# Schematic_2.net
KiCad netlist of a schematic drawn in Altium Designer
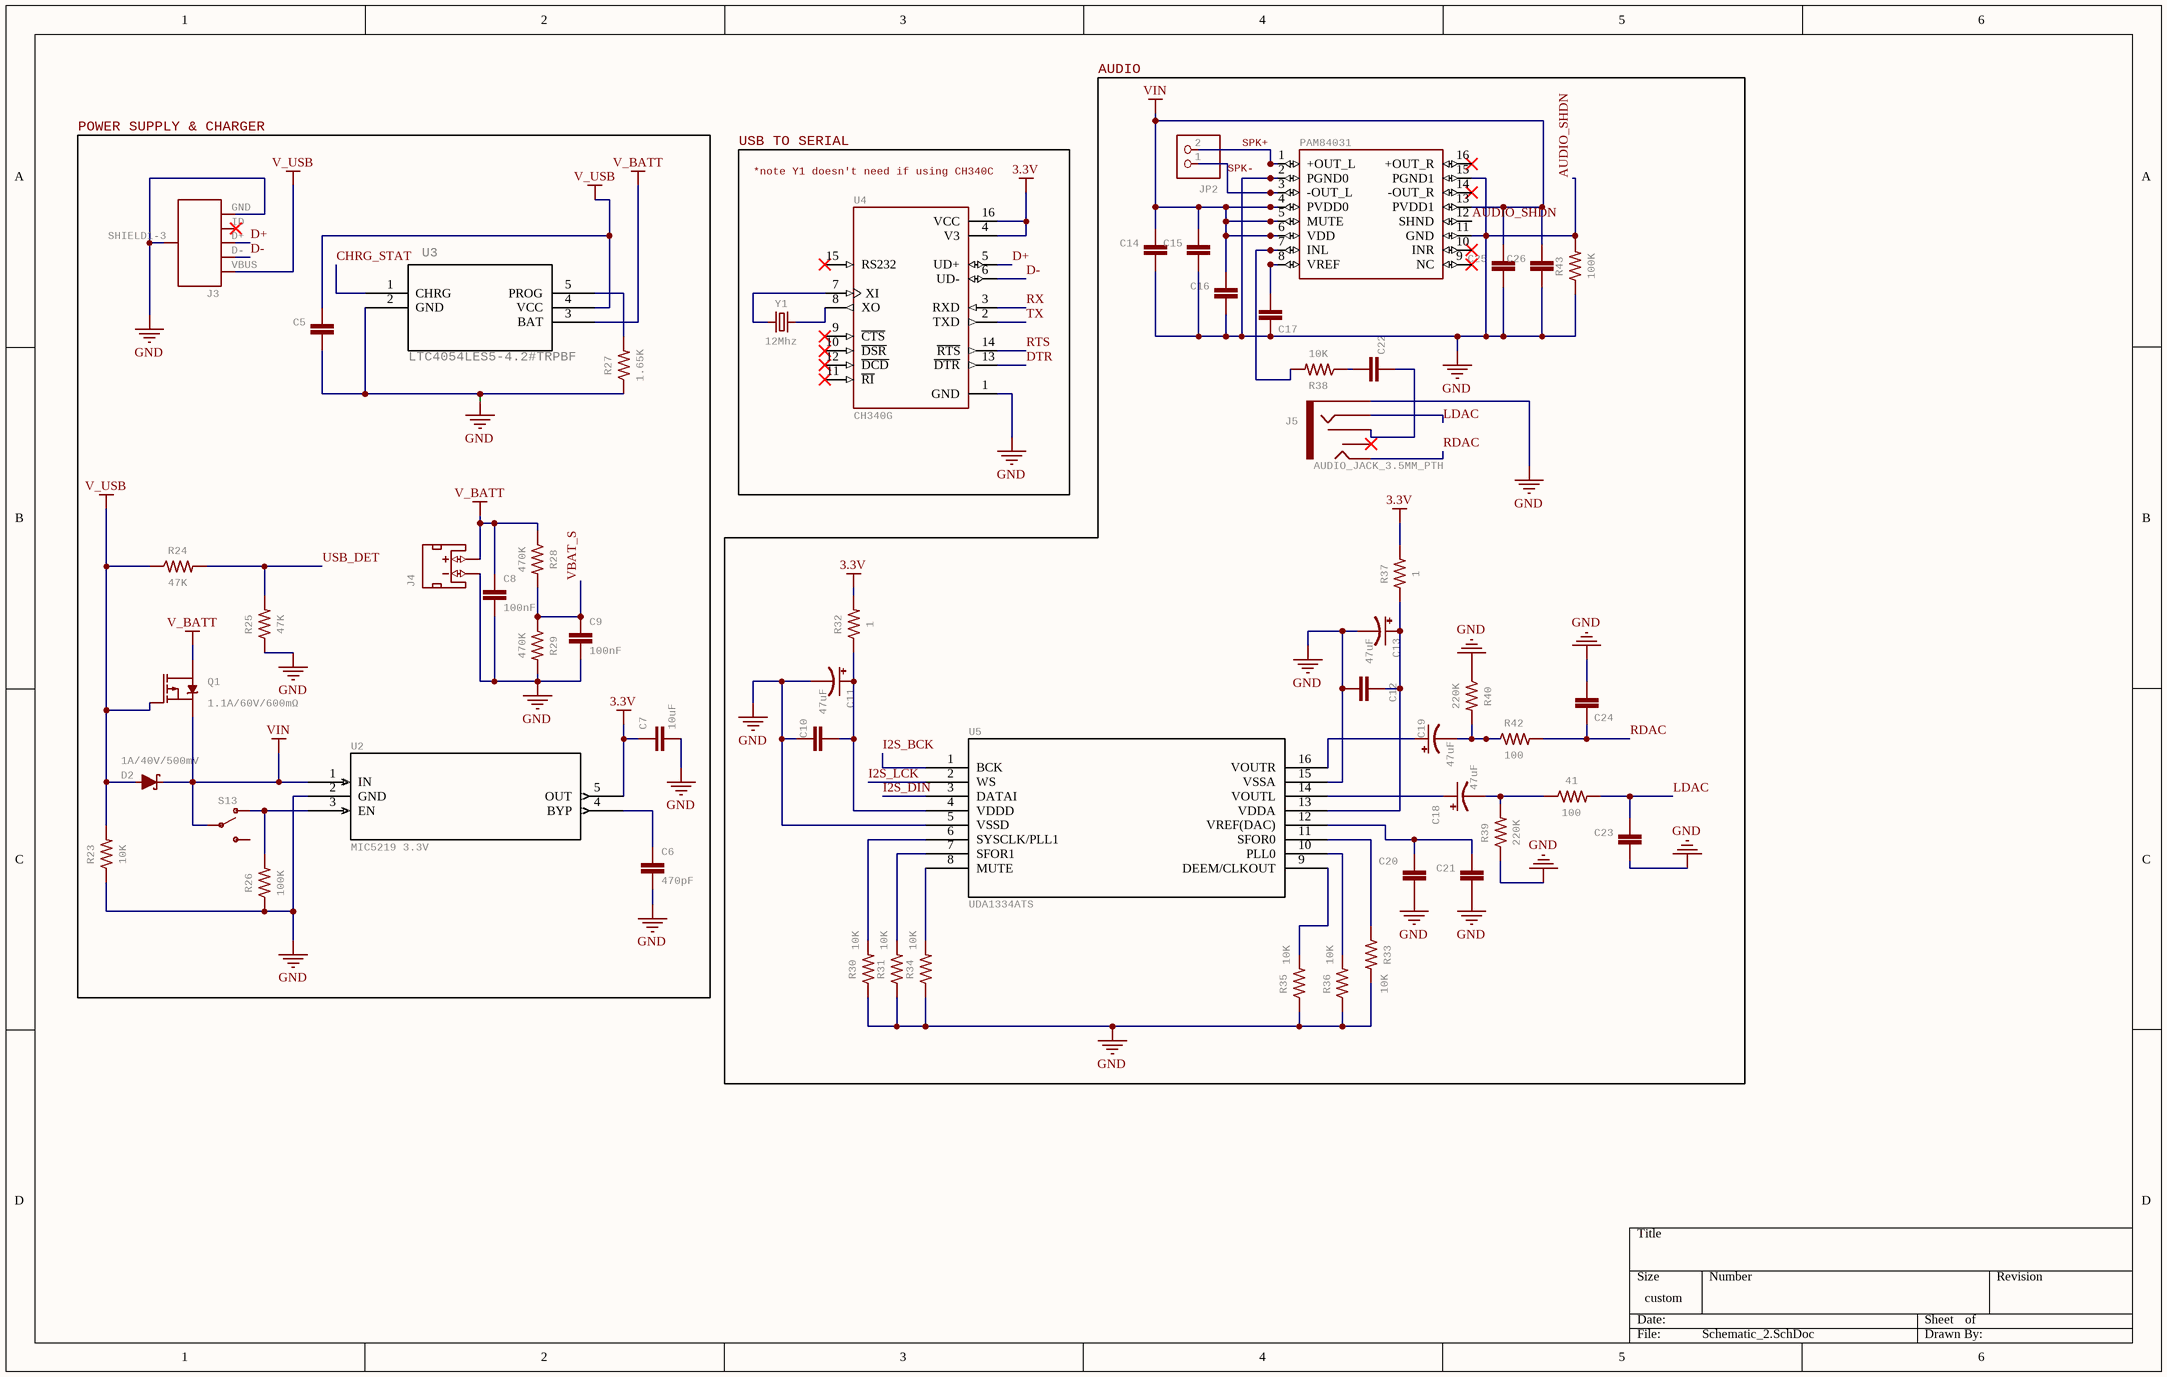
[diagram p0: Schematic_2.SchDoc]

(export (version "E")
  (design (tool "Eeschema 10.0.6"))
  (components
    (comp (ref "41")
      (value "100")
      (footprint "0805 RESISTOR")
      (libsource (lib "2D Components_v1") (part "0.3OHM-0805-1/8W-1%"))
    )
    (comp (ref "C5") (value "~") (footprint "0805") (libsource (lib "") (part "2.2UF-0805-25V-(+80/-20%)_3")))
    (comp (ref "C6")
      (value "470pF")
      (footprint "0805")
      (libsource (lib "2D Components_v1") (part "2.2UF-0805-25V-(+80/-20%)"))
    )
    (comp (ref "C7")
      (value "10uF")
      (footprint "0805")
      (libsource (lib "") (part "2.2UF-0805-25V-(+80/-20%)_1"))
    )
    (comp (ref "C8")
      (value "100nF")
      (footprint "0805")
      (libsource (lib "2D Components_v1") (part "2.2UF-0805-25V-(+80/-20%)"))
    )
    (comp (ref "C9")
      (value "100nF")
      (footprint "0805")
      (libsource (lib "2D Components_v1") (part "2.2UF-0805-25V-(+80/-20%)"))
    )
    (comp (ref "C10")
      (value "~")
      (footprint "0805")
      (libsource (lib "") (part "2.2UF-0805-25V-(+80/-20%)_1"))
    )
    (comp (ref "C11")
      (value "47uF")
      (footprint "EIA3528")
      (libsource (lib "") (part "47UF-POLAR-EIA3528-10V-10%_1"))
    )
    (comp (ref "C12")
      (value "~")
      (footprint "0805")
      (libsource (lib "") (part "2.2UF-0805-25V-(+80/-20%)_1"))
    )
    (comp (ref "C13")
      (value "47uF")
      (footprint "EIA3528")
      (libsource (lib "") (part "47UF-POLAR-EIA3528-10V-10%_1"))
    )
    (comp (ref "C14")
      (value "~")
      (footprint "0805")
      (libsource (lib "") (part "2.2UF-0805-25V-(+80/-20%)_3"))
    )
    (comp (ref "C15")
      (value "~")
      (footprint "0805")
      (libsource (lib "") (part "2.2UF-0805-25V-(+80/-20%)_3"))
    )
    (comp (ref "C16")
      (value "~")
      (footprint "0805")
      (libsource (lib "") (part "2.2UF-0805-25V-(+80/-20%)_3"))
    )
    (comp (ref "C17")
      (value "~")
      (footprint "0805")
      (libsource (lib "") (part "2.2UF-0805-25V-(+80/-20%)_2"))
    )
    (comp (ref "C18")
      (value "47uF")
      (footprint "EIA3528")
      (libsource (lib "2D Components_v1") (part "47UF-POLAR-EIA3528-10V-10%"))
    )
    (comp (ref "C19")
      (value "47uF")
      (footprint "EIA3528")
      (libsource (lib "2D Components_v1") (part "47UF-POLAR-EIA3528-10V-10%"))
    )
    (comp (ref "C20")
      (value "~")
      (footprint "0805")
      (libsource (lib "") (part "2.2UF-0805-25V-(+80/-20%)_3"))
    )
    (comp (ref "C21")
      (value "~")
      (footprint "0805")
      (libsource (lib "") (part "2.2UF-0805-25V-(+80/-20%)_3"))
    )
    (comp (ref "C22")
      (value "~")
      (footprint "0805")
      (libsource (lib "") (part "2.2UF-0805-25V-(+80/-20%)_1"))
    )
    (comp (ref "C23")
      (value "~")
      (footprint "0805")
      (libsource (lib "") (part "2.2UF-0805-25V-(+80/-20%)_3"))
    )
    (comp (ref "C24")
      (value "~")
      (footprint "0805")
      (libsource (lib "2D Components_v1") (part "2.2UF-0805-25V-(+80/-20%)"))
    )
    (comp (ref "C25")
      (value "~")
      (footprint "0805")
      (libsource (lib "") (part "2.2UF-0805-25V-(+80/-20%)_3"))
    )
    (comp (ref "C26")
      (value "~")
      (footprint "0805")
      (libsource (lib "") (part "2.2UF-0805-25V-(+80/-20%)_3"))
    )
    (comp (ref "D2")
      (value "1A/40V/500mV")
      (footprint "SMA-DIODE")
      (libsource (lib "2D Components_v1") (part "DIODE-SCHOTTKY-SS14"))
    )
    (comp (ref "J3")
      (value "~")
      (footprint "USB-B-MICRO-SMD")
      (description "USB_MICRO-B_FEMALE-SMT_J3")
      (libsource (lib "2D Components_v1") (part "USB_MICRO-B_FEMALE-SMT_J3"))
    )
    (comp (ref "J4")
      (value "~")
      (footprint "JST-2-SMD")
      (description "JST_2MM_MALE")
      (libsource (lib "2D Components_v1") (part "JST_2MM_MALE_J4"))
    )
    (comp (ref "J5")
      (value "AUDIO_JACK_3.5MM_PTH")
      (footprint "AUDIO-JACK")
      (libsource (lib "2D Components_v1") (part "AUDIO_JACK_3.5MM_PTH_J5"))
    )
    (comp (ref "JP2")
      (value "~")
      (footprint "1X02M")
      (description "PINHD-1X2_2.00")
      (fields (field (name "LIBRARYNAME") "pinhead-1"))
      (libsource (lib "2D Components_v1") (part "PINHD-1X2_2.00_JP2"))
    )
    (comp (ref "PAM84031")
      (value "PAM8403")
      (footprint "SOP-16")
      (description "Dual channel audio amplifier IC - PAM8403")
      (libsource (lib "2D Components_v1") (part "PAM8403_YES"))
    )
    (comp (ref "Q1")
      (value "1.1A/60V/600mΩ")
      (footprint "SOT23-3")
      (libsource (lib "2D Components_v1") (part "MOSFET_PCH-SI2309DS"))
    )
    (comp (ref "R23")
      (value "10K")
      (footprint "0805")
      (libsource (lib "2D Components_v1") (part "0.22OHM-0805-1/4W-1%"))
    )
    (comp (ref "R24")
      (value "47K")
      (footprint "0805")
      (libsource (lib "2D Components_v1") (part "0.22OHM-0805-1/4W-1%"))
    )
    (comp (ref "R25")
      (value "47K")
      (footprint "0805")
      (libsource (lib "2D Components_v1") (part "0.22OHM-0805-1/4W-1%"))
    )
    (comp (ref "R26")
      (value "100K")
      (footprint "0805")
      (libsource (lib "2D Components_v1") (part "0.22OHM-0805-1/4W-1%"))
    )
    (comp (ref "R27")
      (value "1.65K")
      (footprint "0805")
      (libsource (lib "2D Components_v1") (part "0.3OHM-0805-1/8W-1%"))
    )
    (comp (ref "R28")
      (value "470K")
      (footprint "0805")
      (libsource (lib "2D Components_v1") (part "0.22OHM-0805-1/4W-1%"))
    )
    (comp (ref "R29")
      (value "470K")
      (footprint "0805")
      (libsource (lib "2D Components_v1") (part "0.22OHM-0805-1/4W-1%"))
    )
    (comp (ref "R30")
      (value "10K")
      (footprint "0805")
      (libsource (lib "2D Components_v1") (part "0.3OHM-0805-1/8W-1%"))
    )
    (comp (ref "R31")
      (value "10K")
      (footprint "0805")
      (libsource (lib "2D Components_v1") (part "0.3OHM-0805-1/8W-1%"))
    )
    (comp (ref "R32")
      (value "1")
      (footprint "0805")
      (libsource (lib "2D Components_v1") (part "0.3OHM-0805-1/8W-1%"))
    )
    (comp (ref "R33") (value "10K") (footprint "0805") (libsource (lib "") (part "0.3OHM-0805-1/8W-1%_1")))
    (comp (ref "R34")
      (value "10K")
      (footprint "0805")
      (libsource (lib "2D Components_v1") (part "0.3OHM-0805-1/8W-1%"))
    )
    (comp (ref "R35")
      (value "10K")
      (footprint "0805")
      (libsource (lib "2D Components_v1") (part "0.3OHM-0805-1/8W-1%"))
    )
    (comp (ref "R36")
      (value "10K")
      (footprint "0805")
      (libsource (lib "2D Components_v1") (part "0.3OHM-0805-1/8W-1%"))
    )
    (comp (ref "R37")
      (value "1")
      (footprint "0805")
      (libsource (lib "2D Components_v1") (part "0.3OHM-0805-1/8W-1%"))
    )
    (comp (ref "R38")
      (value "10K")
      (footprint "0805")
      (libsource (lib "2D Components_v1") (part "0.3OHM-0805-1/8W-1%"))
    )
    (comp (ref "R39")
      (value "220K")
      (footprint "0805")
      (libsource (lib "2D Components_v1") (part "0.3OHM-0805-1/8W-1%"))
    )
    (comp (ref "R40")
      (value "220K")
      (footprint "0805")
      (libsource (lib "2D Components_v1") (part "0.3OHM-0805-1/8W-1%"))
    )
    (comp (ref "R42")
      (value "100")
      (footprint "0805")
      (libsource (lib "2D Components_v1") (part "0.3OHM-0805-1/8W-1%"))
    )
    (comp (ref "R43")
      (value "100K")
      (footprint "0805")
      (libsource (lib "2D Components_v1") (part "0.3OHM-0805-1/8W-1%"))
    )
    (comp (ref "S13")
      (value "~")
      (footprint "SWITCH_SPST_SMD_A")
      (libsource (lib "2D Components_v1") (part "SWITCH-SPDT-SMD-RIGHT-ANGLE_1"))
    )
    (comp (ref "U2")
      (value "MIC5219 3.3V")
      (footprint "SOT23-5")
      (libsource (lib "2D Components_v1") (part "V_REG_MIC52195V"))
    )
    (comp (ref "U3")
      (value "LTC4054LES5-4.2#TRPBF")
      (footprint "SOT95P280X100-5N")
      (description "LTC4054LES5-4.2#TRPBF*?")
      (fields
        (field (name "DIGI-KEY_PART_NUMBER") "LTC4054LES5-4.2#TRPBFCT-ND")
        (field (name "MF") "Linear Technology/Analog")
      )
      (libsource (lib "2D Components_v1") (part "LTC4054LES5-4.2#TRPBF_U3"))
    )
    (comp (ref "U4")
      (value "CH340G")
      (footprint "SO016")
      (description "CH340GSMD_SO016")
      (fields (field (name "LIBRARYNAME") "SparkFun-IC-Comms"))
      (libsource (lib "2D Components_v1") (part "CH340GSMD_U4"))
    )
    (comp (ref "U5")
      (value "UDA1334ATS")
      (footprint "MICROBUILDER_SSOP16_4.4MM")
      (description "MICROBUILDER_AUDIO_I2S_UDA1334\"\"")
      (libsource (lib "2D Components_v1") (part "UDA1334_U5"))
    )
    (comp (ref "Y1")
      (value "12Mhz")
      (footprint "CRYSTAL-SMD-5X3.2-4PAD")
      (description "CRYSTALSMD-5X3.2-4PAD")
      (fields (field (name "LIBRARYNAME") "SparkFun-Clocks"))
      (libsource (lib "2D Components_v1") (part "CRYSTALSMD_Y1"))
    )
  )
  (nets
    (net (code "1") (name "/CHRG_STAT") (class "Default")
      (node (ref "U3") (pin "1") (pinfunction "CHRG_1") (pintype "passive"))
    )
    (net (code "2") (name "/D+") (class "Default")
      (node (ref "J3") (pin "D+") (pinfunction "D+_D+") (pintype "bidirectional"))
      (node (ref "U4") (pin "5") (pinfunction "UD+_5") (pintype "bidirectional"))
    )
    (net (code "3") (name "/D-") (class "Default")
      (node (ref "J3") (pin "D-") (pinfunction "D-_D-") (pintype "bidirectional"))
      (node (ref "U4") (pin "6") (pinfunction "UD-_6") (pintype "bidirectional"))
    )
    (net (code "4") (name "/DTR") (class "Default")
      (node (ref "U4") (pin "13") (pinfunction "~{DTR}_13") (pintype "output"))
    )
    (net (code "5") (name "/I2S_BCK") (class "Default")
      (node (ref "U5") (pin "1") (pinfunction "BCK_1") (pintype "passive"))
    )
    (net (code "6") (name "/I2S_DIN") (class "Default")
      (node (ref "U5") (pin "3") (pinfunction "DATAI_3") (pintype "passive"))
    )
    (net (code "7") (name "/I2S_LCK") (class "Default")
      (node (ref "U5") (pin "2") (pinfunction "WS_2") (pintype "passive"))
    )
    (net (code "8") (name "/LDAC") (class "Default")
      (node (ref "41") (pin "2") (pinfunction "2_2") (pintype "passive"))
      (node (ref "C23") (pin "2") (pinfunction "2_2") (pintype "passive"))
      (node (ref "J5") (pin "RING") (pinfunction "RING_RING") (pintype "bidirectional"))
    )
    (net (code "9") (name "/RDAC") (class "Default")
      (node (ref "C24") (pin "2") (pinfunction "2_2") (pintype "passive"))
      (node (ref "J5") (pin "TIP") (pinfunction "TIP_TIP") (pintype "bidirectional"))
      (node (ref "R42") (pin "2") (pinfunction "2_2") (pintype "passive"))
    )
    (net (code "10") (name "/RTS") (class "Default")
      (node (ref "U4") (pin "14") (pinfunction "~{RTS}_14") (pintype "output"))
    )
    (net (code "11") (name "/RX") (class "Default")
      (node (ref "U4") (pin "3") (pinfunction "RXD_3") (pintype "input"))
    )
    (net (code "12") (name "/SPK+") (class "Default")
      (node (ref "JP2") (pin "2") (pinfunction "2_2") (pintype "passive"))
      (node (ref "PAM84031") (pin "1") (pinfunction "+OUT_L_1") (pintype "bidirectional"))
    )
    (net (code "13") (name "/SPK-") (class "Default")
      (node (ref "JP2") (pin "1") (pinfunction "1_1") (pintype "passive"))
      (node (ref "PAM84031") (pin "3") (pinfunction "-OUT_L_3") (pintype "bidirectional"))
    )
    (net (code "14") (name "/TX") (class "Default")
      (node (ref "U4") (pin "2") (pinfunction "TXD_2") (pintype "output"))
    )
    (net (code "15") (name "/USB_DET") (class "Default")
      (node (ref "R24") (pin "2") (pinfunction "2_2") (pintype "passive"))
      (node (ref "R25") (pin "2") (pinfunction "2_2") (pintype "passive"))
    )
    (net (code "16") (name "/VBAT_S") (class "Default")
      (node (ref "C9") (pin "1") (pinfunction "1_1") (pintype "passive"))
      (node (ref "R28") (pin "2") (pinfunction "2_2") (pintype "passive"))
      (node (ref "R29") (pin "1") (pinfunction "1_1") (pintype "passive"))
    )
    (net (code "17") (name "3.3V") (class "Default")
      (node (ref "C7") (pin "1") (pinfunction "1_1") (pintype "passive"))
      (node (ref "R32") (pin "2") (pinfunction "2_2") (pintype "passive"))
      (node (ref "R37") (pin "2") (pinfunction "2_2") (pintype "passive"))
      (node (ref "U2") (pin "5") (pinfunction "OUT_5") (pintype "output"))
      (node (ref "U4") (pin "16") (pinfunction "VCC_16") (pintype "power_in"))
      (node (ref "U4") (pin "4") (pinfunction "V3_4") (pintype "power_in"))
    )
    (net (code "18") (name "GND") (class "Default")
      (node (ref "C10") (pin "1") (pinfunction "1_1") (pintype "passive"))
      (node (ref "C11") (pin "C") (pinfunction "-_C") (pintype "passive"))
      (node (ref "C12") (pin "1") (pinfunction "1_1") (pintype "passive"))
      (node (ref "C13") (pin "C") (pinfunction "-_C") (pintype "passive"))
      (node (ref "C14") (pin "1") (pinfunction "1_1") (pintype "passive"))
      (node (ref "C15") (pin "1") (pinfunction "1_1") (pintype "passive"))
      (node (ref "C16") (pin "1") (pinfunction "1_1") (pintype "passive"))
      (node (ref "C17") (pin "1") (pinfunction "1_1") (pintype "passive"))
      (node (ref "C20") (pin "1") (pinfunction "1_1") (pintype "passive"))
      (node (ref "C21") (pin "1") (pinfunction "1_1") (pintype "passive"))
      (node (ref "C23") (pin "1") (pinfunction "1_1") (pintype "passive"))
      (node (ref "C24") (pin "1") (pinfunction "1_1") (pintype "passive"))
      (node (ref "C25") (pin "1") (pinfunction "1_1") (pintype "passive"))
      (node (ref "C26") (pin "1") (pinfunction "1_1") (pintype "passive"))
      (node (ref "C5") (pin "1") (pinfunction "1_1") (pintype "passive"))
      (node (ref "C6") (pin "2") (pinfunction "2_2") (pintype "passive"))
      (node (ref "C7") (pin "2") (pinfunction "2_2") (pintype "passive"))
      (node (ref "C8") (pin "2") (pinfunction "2_2") (pintype "passive"))
      (node (ref "C9") (pin "2") (pinfunction "2_2") (pintype "passive"))
      (node (ref "J3") (pin "GND") (pinfunction "GND_GND") (pintype "power_in"))
      (node (ref "J3") (pin "SHIELD1-3") (pinfunction "SHIELD_SHIELD1-3") (pintype "bidirectional"))
      (node (ref "J4") (pin "1") (pinfunction "-_1") (pintype "bidirectional"))
      (node (ref "J5") (pin "SLEEVE") (pinfunction "SLEEVE_SLEEVE") (pintype "bidirectional"))
      (node (ref "PAM84031") (pin "11") (pinfunction "GND_11") (pintype "bidirectional"))
      (node (ref "PAM84031") (pin "12") (pinfunction "SHND_12") (pintype "bidirectional"))
      (node (ref "PAM84031") (pin "15") (pinfunction "PGND1_15") (pintype "bidirectional"))
      (node (ref "PAM84031") (pin "2") (pinfunction "PGND0_2") (pintype "bidirectional"))
      (node (ref "R23") (pin "1") (pinfunction "1_1") (pintype "passive"))
      (node (ref "R25") (pin "1") (pinfunction "1_1") (pintype "passive"))
      (node (ref "R26") (pin "1") (pinfunction "1_1") (pintype "passive"))
      (node (ref "R27") (pin "1") (pinfunction "1_1") (pintype "passive"))
      (node (ref "R29") (pin "2") (pinfunction "2_2") (pintype "passive"))
      (node (ref "R30") (pin "1") (pinfunction "1_1") (pintype "passive"))
      (node (ref "R31") (pin "1") (pinfunction "1_1") (pintype "passive"))
      (node (ref "R33") (pin "1") (pinfunction "1_1") (pintype "passive"))
      (node (ref "R34") (pin "1") (pinfunction "1_1") (pintype "passive"))
      (node (ref "R35") (pin "1") (pinfunction "1_1") (pintype "passive"))
      (node (ref "R36") (pin "1") (pinfunction "1_1") (pintype "passive"))
      (node (ref "R39") (pin "1") (pinfunction "1_1") (pintype "passive"))
      (node (ref "R40") (pin "1") (pinfunction "1_1") (pintype "passive"))
      (node (ref "R43") (pin "1") (pinfunction "1_1") (pintype "passive"))
      (node (ref "R43") (pin "2") (pinfunction "2_2") (pintype "passive"))
      (node (ref "U2") (pin "2") (pinfunction "GND_2") (pintype "power_in"))
      (node (ref "U3") (pin "2") (pinfunction "GND_2") (pintype "power_in"))
      (node (ref "U4") (pin "1") (pinfunction "GND_1") (pintype "power_in"))
      (node (ref "U5") (pin "15") (pinfunction "VSSA_15") (pintype "passive"))
      (node (ref "U5") (pin "5") (pinfunction "VSSD_5") (pintype "passive"))
    )
    (net (code "19") (name "Net-(C11-+)") (class "Default")
      (node (ref "C10") (pin "2") (pinfunction "2_2") (pintype "passive"))
      (node (ref "C11") (pin "A") (pinfunction "+_A") (pintype "passive"))
      (node (ref "R32") (pin "1") (pinfunction "1_1") (pintype "passive"))
      (node (ref "U5") (pin "4") (pinfunction "VDDD_4") (pintype "passive"))
    )
    (net (code "20") (name "Net-(C13-+)") (class "Default")
      (node (ref "C12") (pin "2") (pinfunction "2_2") (pintype "passive"))
      (node (ref "C13") (pin "A") (pinfunction "+_A") (pintype "passive"))
      (node (ref "R37") (pin "1") (pinfunction "1_1") (pintype "passive"))
      (node (ref "U5") (pin "13") (pinfunction "VDDA_13") (pintype "passive"))
    )
    (net (code "21") (name "Net-(C18-+)") (class "Default")
      (node (ref "C18") (pin "A") (pinfunction "+_A") (pintype "passive"))
      (node (ref "U5") (pin "14") (pinfunction "VOUTL_14") (pintype "passive"))
    )
    (net (code "22") (name "Net-(C18--)") (class "Default")
      (node (ref "41") (pin "1") (pinfunction "1_1") (pintype "passive"))
      (node (ref "C18") (pin "C") (pinfunction "-_C") (pintype "passive"))
      (node (ref "R39") (pin "2") (pinfunction "2_2") (pintype "passive"))
    )
    (net (code "23") (name "Net-(C19-+)") (class "Default")
      (node (ref "C19") (pin "A") (pinfunction "+_A") (pintype "passive"))
      (node (ref "U5") (pin "16") (pinfunction "VOUTR_16") (pintype "passive"))
    )
    (net (code "24") (name "Net-(C19--)") (class "Default")
      (node (ref "C19") (pin "C") (pinfunction "-_C") (pintype "passive"))
      (node (ref "R40") (pin "2") (pinfunction "2_2") (pintype "passive"))
      (node (ref "R42") (pin "1") (pinfunction "1_1") (pintype "passive"))
    )
    (net (code "25") (name "Net-(C22-Pad1)") (class "Default")
      (node (ref "C22") (pin "1") (pinfunction "1_1") (pintype "passive"))
      (node (ref "R38") (pin "1") (pinfunction "1_1") (pintype "passive"))
    )
    (net (code "26") (name "Net-(C22-Pad2)") (class "Default")
      (node (ref "C22") (pin "2") (pinfunction "2_2") (pintype "passive"))
      (node (ref "J5") (pin "RSH") (pinfunction "RSH_RSH") (pintype "bidirectional"))
    )
    (net (code "27") (name "Net-(PAM84031-INL)") (class "Default")
      (node (ref "PAM84031") (pin "7") (pinfunction "INL_7") (pintype "bidirectional"))
      (node (ref "R38") (pin "2") (pinfunction "2_2") (pintype "passive"))
    )
    (net (code "28") (name "Net-(PAM84031-VREF)") (class "Default")
      (node (ref "C17") (pin "2") (pinfunction "2_2") (pintype "passive"))
      (node (ref "PAM84031") (pin "8") (pinfunction "VREF_8") (pintype "bidirectional"))
    )
    (net (code "29") (name "Net-(S13-O)") (class "Default")
      (node (ref "R26") (pin "2") (pinfunction "2_2") (pintype "passive"))
      (node (ref "S13") (pin "1") (pinfunction "O_1") (pintype "passive"))
      (node (ref "U2") (pin "3") (pinfunction "EN_3") (pintype "input"))
    )
    (net (code "30") (name "Net-(U2-BYP)") (class "Default")
      (node (ref "C6") (pin "1") (pinfunction "1_1") (pintype "passive"))
      (node (ref "U2") (pin "4") (pinfunction "BYP_4") (pintype "output"))
    )
    (net (code "31") (name "Net-(U3-PROG)") (class "Default")
      (node (ref "R27") (pin "2") (pinfunction "2_2") (pintype "passive"))
      (node (ref "U3") (pin "5") (pinfunction "PROG_5") (pintype "passive"))
    )
    (net (code "32") (name "Net-(U4-XI)") (class "Default")
      (node (ref "U4") (pin "7") (pinfunction "XI_7") (pintype "input"))
      (node (ref "Y1") (pin "3") (pinfunction "2_3") (pintype "passive"))
    )
    (net (code "33") (name "Net-(U4-XO)") (class "Default")
      (node (ref "U4") (pin "8") (pinfunction "XO_8") (pintype "output"))
      (node (ref "Y1") (pin "1") (pinfunction "1_1") (pintype "passive"))
    )
    (net (code "34") (name "Net-(U5-DEEM{slash}CLKOUT)") (class "Default")
      (node (ref "R35") (pin "2") (pinfunction "2_2") (pintype "passive"))
      (node (ref "U5") (pin "9") (pinfunction "DEEM/CLKOUT_9") (pintype "passive"))
    )
    (net (code "35") (name "Net-(U5-MUTE)") (class "Default")
      (node (ref "R34") (pin "2") (pinfunction "2_2") (pintype "passive"))
      (node (ref "U5") (pin "8") (pinfunction "MUTE_8") (pintype "passive"))
    )
    (net (code "36") (name "Net-(U5-PLL0)") (class "Default")
      (node (ref "R36") (pin "2") (pinfunction "2_2") (pintype "passive"))
      (node (ref "U5") (pin "10") (pinfunction "PLL0_10") (pintype "passive"))
    )
    (net (code "37") (name "Net-(U5-SFOR0)") (class "Default")
      (node (ref "R33") (pin "2") (pinfunction "2_2") (pintype "passive"))
      (node (ref "U5") (pin "11") (pinfunction "SFOR0_11") (pintype "passive"))
    )
    (net (code "38") (name "Net-(U5-SFOR1)") (class "Default")
      (node (ref "R31") (pin "2") (pinfunction "2_2") (pintype "passive"))
      (node (ref "U5") (pin "7") (pinfunction "SFOR1_7") (pintype "passive"))
    )
    (net (code "39") (name "Net-(U5-SYSCLK{slash}PLL1)") (class "Default")
      (node (ref "R30") (pin "2") (pinfunction "2_2") (pintype "passive"))
      (node (ref "U5") (pin "6") (pinfunction "SYSCLK/PLL1_6") (pintype "passive"))
    )
    (net (code "40") (name "Net-(U5-VREF(DAC))") (class "Default")
      (node (ref "C20") (pin "2") (pinfunction "2_2") (pintype "passive"))
      (node (ref "C21") (pin "2") (pinfunction "2_2") (pintype "passive"))
      (node (ref "U5") (pin "12") (pinfunction "VREF(DAC)_12") (pintype "passive"))
    )
    (net (code "41") (name "VIN") (class "Default")
      (node (ref "C14") (pin "2") (pinfunction "2_2") (pintype "passive"))
      (node (ref "C15") (pin "2") (pinfunction "2_2") (pintype "passive"))
      (node (ref "C16") (pin "2") (pinfunction "2_2") (pintype "passive"))
      (node (ref "C25") (pin "2") (pinfunction "2_2") (pintype "passive"))
      (node (ref "C26") (pin "2") (pinfunction "2_2") (pintype "passive"))
      (node (ref "D2") (pin "C") (pinfunction "C_C") (pintype "passive"))
      (node (ref "PAM84031") (pin "13") (pinfunction "PVDD1_13") (pintype "bidirectional"))
      (node (ref "PAM84031") (pin "4") (pinfunction "PVDD0_4") (pintype "bidirectional"))
      (node (ref "PAM84031") (pin "5") (pinfunction "MUTE_5") (pintype "bidirectional"))
      (node (ref "PAM84031") (pin "6") (pinfunction "VDD_6") (pintype "bidirectional"))
      (node (ref "Q1") (pin "2") (pinfunction "S_2") (pintype "bidirectional"))
      (node (ref "S13") (pin "2") (pinfunction "P_2") (pintype "passive"))
      (node (ref "U2") (pin "1") (pinfunction "IN_1") (pintype "input"))
    )
    (net (code "42") (name "V_BATT") (class "Default")
      (node (ref "C8") (pin "1") (pinfunction "1_1") (pintype "passive"))
      (node (ref "J4") (pin "2") (pinfunction "+_2") (pintype "bidirectional"))
      (node (ref "Q1") (pin "3") (pinfunction "D_3") (pintype "bidirectional"))
      (node (ref "R28") (pin "1") (pinfunction "1_1") (pintype "passive"))
      (node (ref "U3") (pin "3") (pinfunction "BAT_3") (pintype "passive"))
    )
    (net (code "43") (name "V_USB") (class "Default")
      (node (ref "C5") (pin "2") (pinfunction "2_2") (pintype "passive"))
      (node (ref "D2") (pin "A") (pinfunction "A_A") (pintype "passive"))
      (node (ref "J3") (pin "VBUS") (pinfunction "VBUS_VBUS") (pintype "power_in"))
      (node (ref "Q1") (pin "1") (pinfunction "G_1") (pintype "bidirectional"))
      (node (ref "R23") (pin "2") (pinfunction "2_2") (pintype "passive"))
      (node (ref "R24") (pin "1") (pinfunction "1_1") (pintype "passive"))
      (node (ref "U3") (pin "4") (pinfunction "VCC_4") (pintype "power_in"))
    )
    (net (code "44") (name "unconnected-(J3-PadID)") (class "Default")
      (node (ref "J3") (pin "ID") (pinfunction "ID_ID") (pintype "bidirectional+no_connect"))
    )
    (net (code "45") (name "unconnected-(J4-PAD1-PadNC1)") (class "Default")
      (node (ref "J4") (pin "NC1") (pinfunction "PAD1_NC1") (pintype "bidirectional"))
    )
    (net (code "46") (name "unconnected-(J4-PAD2-PadNC2)") (class "Default")
      (node (ref "J4") (pin "NC2") (pinfunction "PAD2_NC2") (pintype "bidirectional"))
    )
    (net (code "47") (name "unconnected-(J5-PadTSH)") (class "Default")
      (node (ref "J5") (pin "TSH") (pinfunction "TSH_TSH") (pintype "bidirectional+no_connect"))
    )
    (net (code "48") (name "unconnected-(PAM84031-+OUT_R-Pad16)") (class "Default")
      (node (ref "PAM84031") (pin "16") (pinfunction "+OUT_R_16") (pintype "bidirectional+no_connect"))
    )
    (net (code "49") (name "unconnected-(PAM84031--OUT_R-Pad14)") (class "Default")
      (node (ref "PAM84031") (pin "14") (pinfunction "-OUT_R_14") (pintype "bidirectional+no_connect"))
    )
    (net (code "50") (name "unconnected-(PAM84031-INR-Pad10)") (class "Default")
      (node (ref "PAM84031") (pin "10") (pinfunction "INR_10") (pintype "bidirectional+no_connect"))
    )
    (net (code "51") (name "unconnected-(PAM84031-NC-Pad9)") (class "Default")
      (node (ref "PAM84031") (pin "9") (pinfunction "NC_9") (pintype "bidirectional+no_connect"))
    )
    (net (code "52") (name "unconnected-(S13-S-Pad3)") (class "Default")
      (node (ref "S13") (pin "3") (pinfunction "S_3") (pintype "passive"))
    )
    (net (code "53") (name "unconnected-(U4-RS232-Pad15)") (class "Default")
      (node (ref "U4") (pin "15") (pinfunction "RS232_15") (pintype "input+no_connect"))
    )
    (net (code "54") (name "unconnected-(U4-~{CTS}-Pad9)") (class "Default")
      (node (ref "U4") (pin "9") (pinfunction "~{CTS}_9") (pintype "input+no_connect"))
    )
    (net (code "55") (name "unconnected-(U4-~{DCD}-Pad12)") (class "Default")
      (node (ref "U4") (pin "12") (pinfunction "~{DCD}_12") (pintype "input+no_connect"))
    )
    (net (code "56") (name "unconnected-(U4-~{DSR}-Pad10)") (class "Default")
      (node (ref "U4") (pin "10") (pinfunction "~{DSR}_10") (pintype "input+no_connect"))
    )
    (net (code "57") (name "unconnected-(U4-~{RI}-Pad11)") (class "Default")
      (node (ref "U4") (pin "11") (pinfunction "~{RI}_11") (pintype "input+no_connect"))
    )
  )
)
